# FetherV2.net
KiCad netlist of a schematic drawn in EAGLE
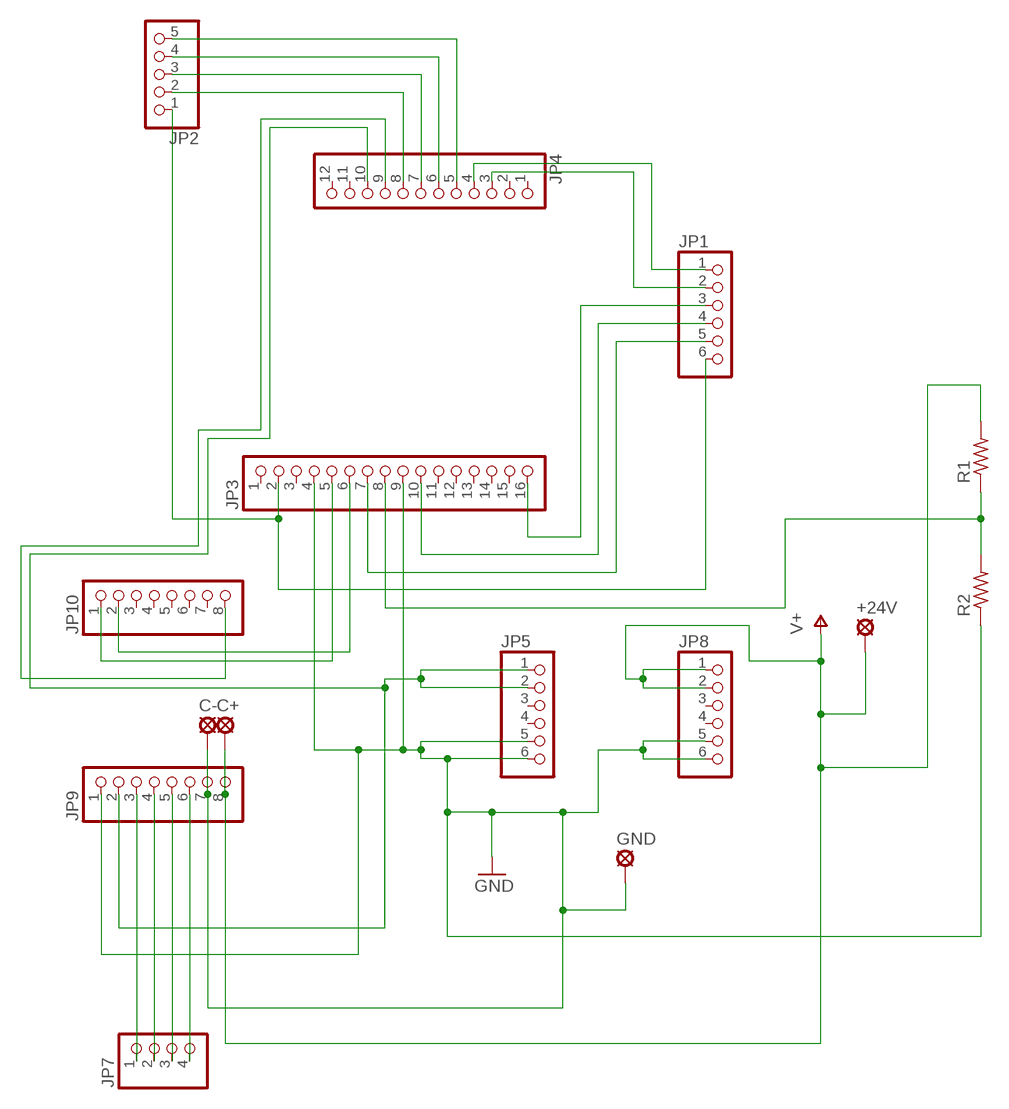
[diagram p0: schematic, sheet 1]

(export (version "E")
  (design (tool "Eeschema 10.0.6"))
  (components
    (comp (ref "+24V")
      (value "SE14")
      (footprint "eagle-import:SE14")
      (libsource (lib "eagle-import") (part "SE14"))
    )
    (comp (ref "C+")
      (value "SE14")
      (footprint "eagle-import:SE14")
      (libsource (lib "eagle-import") (part "SE14"))
    )
    (comp (ref "C-")
      (value "SE14")
      (footprint "eagle-import:SE14")
      (libsource (lib "eagle-import") (part "SE14"))
    )
    (comp (ref "GND")
      (value "SE14")
      (footprint "eagle-import:SE14")
      (libsource (lib "eagle-import") (part "SE14"))
    )
    (comp (ref "JP1")
      (value "PINHD-1X6/90")
      (footprint "eagle-import:1X06_90")
      (libsource (lib "eagle-import") (part "PINHD-1X6/90"))
    )
    (comp (ref "JP2")
      (value "PINHD-1X5/90")
      (footprint "eagle-import:1X05_90")
      (libsource (lib "eagle-import") (part "PINHD-1X5/90"))
    )
    (comp (ref "JP3")
      (value "PINHD-1X16")
      (footprint "eagle-import:1X16")
      (libsource (lib "eagle-import") (part "PINHD-1X16"))
    )
    (comp (ref "JP4")
      (value "PINHD-1X12")
      (footprint "eagle-import:1X12")
      (libsource (lib "eagle-import") (part "PINHD-1X12"))
    )
    (comp (ref "JP5")
      (value "PINHD-1X6")
      (footprint "eagle-import:1X06")
      (libsource (lib "eagle-import") (part "PINHD-1X6"))
    )
    (comp (ref "JP7")
      (value "PINHD-1X4")
      (footprint "eagle-import:1X04")
      (libsource (lib "eagle-import") (part "PINHD-1X4"))
    )
    (comp (ref "JP8")
      (value "PINHD-1X6")
      (footprint "eagle-import:1X06")
      (libsource (lib "eagle-import") (part "PINHD-1X6"))
    )
    (comp (ref "JP9")
      (value "PINHD-1X8")
      (footprint "eagle-import:1X08")
      (libsource (lib "eagle-import") (part "PINHD-1X8"))
    )
    (comp (ref "JP10")
      (value "PINHD-1X8")
      (footprint "eagle-import:1X08")
      (libsource (lib "eagle-import") (part "PINHD-1X8"))
    )
    (comp (ref "R1")
      (value "FLIPFLOP-RES")
      (footprint "eagle-import:0805-THM")
      (libsource (lib "eagle-import") (part "FLIPFLOP-RES"))
    )
    (comp (ref "R2")
      (value "FLIPFLOP-RES")
      (footprint "eagle-import:0805-THM")
      (libsource (lib "eagle-import") (part "FLIPFLOP-RES"))
    )
  )
  (nets
    (net (code "1") (name "GND") (class "Default")
      (node (ref "C-") (pin "MP") (pinfunction "MP_MP") (pintype "passive"))
      (node (ref "GND") (pin "MP") (pinfunction "MP_MP") (pintype "passive"))
      (node (ref "JP3") (pin "4") (pinfunction "4_4") (pintype "passive"))
      (node (ref "JP3") (pin "9") (pinfunction "9_9") (pintype "passive"))
      (node (ref "JP5") (pin "5") (pinfunction "5_5") (pintype "passive"))
      (node (ref "JP5") (pin "6") (pinfunction "6_6") (pintype "passive"))
      (node (ref "JP8") (pin "5") (pinfunction "5_5") (pintype "passive"))
      (node (ref "JP8") (pin "6") (pinfunction "6_6") (pintype "passive"))
      (node (ref "JP9") (pin "1") (pinfunction "1_1") (pintype "passive"))
      (node (ref "JP9") (pin "7") (pinfunction "7_7") (pintype "passive"))
      (node (ref "R2") (pin "1") (pinfunction "1_1") (pintype "passive"))
    )
    (net (code "2") (name "Net-(JP1-Pad1)") (class "Default")
      (node (ref "JP1") (pin "1") (pinfunction "1_1") (pintype "passive"))
      (node (ref "JP4") (pin "4") (pinfunction "4_4") (pintype "passive"))
    )
    (net (code "3") (name "Net-(JP1-Pad2)") (class "Default")
      (node (ref "JP1") (pin "2") (pinfunction "2_2") (pintype "passive"))
      (node (ref "JP4") (pin "3") (pinfunction "3_3") (pintype "passive"))
    )
    (net (code "4") (name "Net-(JP1-Pad3)") (class "Default")
      (node (ref "JP1") (pin "3") (pinfunction "3_3") (pintype "passive"))
      (node (ref "JP3") (pin "16") (pinfunction "16_16") (pintype "passive"))
    )
    (net (code "5") (name "Net-(JP1-Pad4)") (class "Default")
      (node (ref "JP1") (pin "4") (pinfunction "4_4") (pintype "passive"))
      (node (ref "JP3") (pin "10") (pinfunction "10_10") (pintype "passive"))
    )
    (net (code "6") (name "Net-(JP1-Pad5)") (class "Default")
      (node (ref "JP1") (pin "5") (pinfunction "5_5") (pintype "passive"))
      (node (ref "JP3") (pin "7") (pinfunction "7_7") (pintype "passive"))
    )
    (net (code "7") (name "Net-(JP1-Pad6)") (class "Default")
      (node (ref "JP1") (pin "6") (pinfunction "6_6") (pintype "passive"))
      (node (ref "JP2") (pin "1") (pinfunction "1_1") (pintype "passive"))
      (node (ref "JP3") (pin "2") (pinfunction "2_2") (pintype "passive"))
    )
    (net (code "8") (name "Net-(JP2-Pad2)") (class "Default")
      (node (ref "JP2") (pin "2") (pinfunction "2_2") (pintype "passive"))
      (node (ref "JP4") (pin "8") (pinfunction "8_8") (pintype "passive"))
    )
    (net (code "9") (name "Net-(JP2-Pad3)") (class "Default")
      (node (ref "JP2") (pin "3") (pinfunction "3_3") (pintype "passive"))
      (node (ref "JP4") (pin "7") (pinfunction "7_7") (pintype "passive"))
    )
    (net (code "10") (name "Net-(JP2-Pad4)") (class "Default")
      (node (ref "JP2") (pin "4") (pinfunction "4_4") (pintype "passive"))
      (node (ref "JP4") (pin "6") (pinfunction "6_6") (pintype "passive"))
    )
    (net (code "11") (name "Net-(JP2-Pad5)") (class "Default")
      (node (ref "JP2") (pin "5") (pinfunction "5_5") (pintype "passive"))
      (node (ref "JP4") (pin "5") (pinfunction "5_5") (pintype "passive"))
    )
    (net (code "12") (name "Net-(JP3-Pad8)") (class "Default")
      (node (ref "JP3") (pin "8") (pinfunction "8_8") (pintype "passive"))
      (node (ref "R1") (pin "1") (pinfunction "1_1") (pintype "passive"))
      (node (ref "R2") (pin "2") (pinfunction "2_2") (pintype "passive"))
    )
    (net (code "13") (name "Net-(JP4-Pad10)") (class "Default")
      (node (ref "JP4") (pin "10") (pinfunction "10_10") (pintype "passive"))
      (node (ref "JP5") (pin "1") (pinfunction "1_1") (pintype "passive"))
      (node (ref "JP5") (pin "2") (pinfunction "2_2") (pintype "passive"))
      (node (ref "JP9") (pin "2") (pinfunction "2_2") (pintype "passive"))
    )
    (net (code "14") (name "Net-(JP7-Pad1)") (class "Default")
      (node (ref "JP7") (pin "1") (pinfunction "1_1") (pintype "passive"))
      (node (ref "JP9") (pin "3") (pinfunction "3_3") (pintype "passive"))
    )
    (net (code "15") (name "Net-(JP7-Pad2)") (class "Default")
      (node (ref "JP7") (pin "2") (pinfunction "2_2") (pintype "passive"))
      (node (ref "JP9") (pin "4") (pinfunction "4_4") (pintype "passive"))
    )
    (net (code "16") (name "Net-(JP7-Pad3)") (class "Default")
      (node (ref "JP7") (pin "3") (pinfunction "3_3") (pintype "passive"))
      (node (ref "JP9") (pin "5") (pinfunction "5_5") (pintype "passive"))
    )
    (net (code "17") (name "Net-(JP7-Pad4)") (class "Default")
      (node (ref "JP7") (pin "4") (pinfunction "4_4") (pintype "passive"))
      (node (ref "JP9") (pin "6") (pinfunction "6_6") (pintype "passive"))
    )
    (net (code "18") (name "Net-(JP10-Pad1)") (class "Default")
      (node (ref "JP10") (pin "1") (pinfunction "1_1") (pintype "passive"))
      (node (ref "JP3") (pin "5") (pinfunction "5_5") (pintype "passive"))
    )
    (net (code "19") (name "Net-(JP10-Pad2)") (class "Default")
      (node (ref "JP10") (pin "2") (pinfunction "2_2") (pintype "passive"))
      (node (ref "JP3") (pin "6") (pinfunction "6_6") (pintype "passive"))
    )
    (net (code "20") (name "Net-(JP10-Pad8)") (class "Default")
      (node (ref "JP10") (pin "8") (pinfunction "8_8") (pintype "passive"))
      (node (ref "JP4") (pin "9") (pinfunction "9_9") (pintype "passive"))
    )
    (net (code "21") (name "V+") (class "Default")
      (node (ref "+24V") (pin "MP") (pinfunction "MP_MP") (pintype "passive"))
      (node (ref "C+") (pin "MP") (pinfunction "MP_MP") (pintype "passive"))
      (node (ref "JP8") (pin "1") (pinfunction "1_1") (pintype "passive"))
      (node (ref "JP8") (pin "2") (pinfunction "2_2") (pintype "passive"))
      (node (ref "JP9") (pin "8") (pinfunction "8_8") (pintype "passive"))
      (node (ref "R1") (pin "2") (pinfunction "2_2") (pintype "passive"))
    )
    (net (code "22") (name "unconnected-(JP3-Pad1)") (class "Default")
      (node (ref "JP3") (pin "1") (pinfunction "1_1") (pintype "passive"))
    )
    (net (code "23") (name "unconnected-(JP3-Pad3)") (class "Default")
      (node (ref "JP3") (pin "3") (pinfunction "3_3") (pintype "passive"))
    )
    (net (code "24") (name "unconnected-(JP3-Pad11)") (class "Default")
      (node (ref "JP3") (pin "11") (pinfunction "11_11") (pintype "passive"))
    )
    (net (code "25") (name "unconnected-(JP3-Pad12)") (class "Default")
      (node (ref "JP3") (pin "12") (pinfunction "12_12") (pintype "passive"))
    )
    (net (code "26") (name "unconnected-(JP3-Pad13)") (class "Default")
      (node (ref "JP3") (pin "13") (pinfunction "13_13") (pintype "passive"))
    )
    (net (code "27") (name "unconnected-(JP3-Pad14)") (class "Default")
      (node (ref "JP3") (pin "14") (pinfunction "14_14") (pintype "passive"))
    )
    (net (code "28") (name "unconnected-(JP3-Pad15)") (class "Default")
      (node (ref "JP3") (pin "15") (pinfunction "15_15") (pintype "passive"))
    )
    (net (code "29") (name "unconnected-(JP4-Pad1)") (class "Default")
      (node (ref "JP4") (pin "1") (pinfunction "1_1") (pintype "passive"))
    )
    (net (code "30") (name "unconnected-(JP4-Pad2)") (class "Default")
      (node (ref "JP4") (pin "2") (pinfunction "2_2") (pintype "passive"))
    )
    (net (code "31") (name "unconnected-(JP4-Pad11)") (class "Default")
      (node (ref "JP4") (pin "11") (pinfunction "11_11") (pintype "passive"))
    )
    (net (code "32") (name "unconnected-(JP4-Pad12)") (class "Default")
      (node (ref "JP4") (pin "12") (pinfunction "12_12") (pintype "passive"))
    )
    (net (code "33") (name "unconnected-(JP5-Pad3)") (class "Default")
      (node (ref "JP5") (pin "3") (pinfunction "3_3") (pintype "passive"))
    )
    (net (code "34") (name "unconnected-(JP5-Pad4)") (class "Default")
      (node (ref "JP5") (pin "4") (pinfunction "4_4") (pintype "passive"))
    )
    (net (code "35") (name "unconnected-(JP8-Pad3)") (class "Default")
      (node (ref "JP8") (pin "3") (pinfunction "3_3") (pintype "passive"))
    )
    (net (code "36") (name "unconnected-(JP8-Pad4)") (class "Default")
      (node (ref "JP8") (pin "4") (pinfunction "4_4") (pintype "passive"))
    )
    (net (code "37") (name "unconnected-(JP10-Pad3)") (class "Default")
      (node (ref "JP10") (pin "3") (pinfunction "3_3") (pintype "passive"))
    )
    (net (code "38") (name "unconnected-(JP10-Pad4)") (class "Default")
      (node (ref "JP10") (pin "4") (pinfunction "4_4") (pintype "passive"))
    )
    (net (code "39") (name "unconnected-(JP10-Pad5)") (class "Default")
      (node (ref "JP10") (pin "5") (pinfunction "5_5") (pintype "passive"))
    )
    (net (code "40") (name "unconnected-(JP10-Pad6)") (class "Default")
      (node (ref "JP10") (pin "6") (pinfunction "6_6") (pintype "passive"))
    )
    (net (code "41") (name "unconnected-(JP10-Pad7)") (class "Default")
      (node (ref "JP10") (pin "7") (pinfunction "7_7") (pintype "passive"))
    )
  )
)
